# Sheet2.net
KiCad netlist of a schematic drawn in Altium Designer
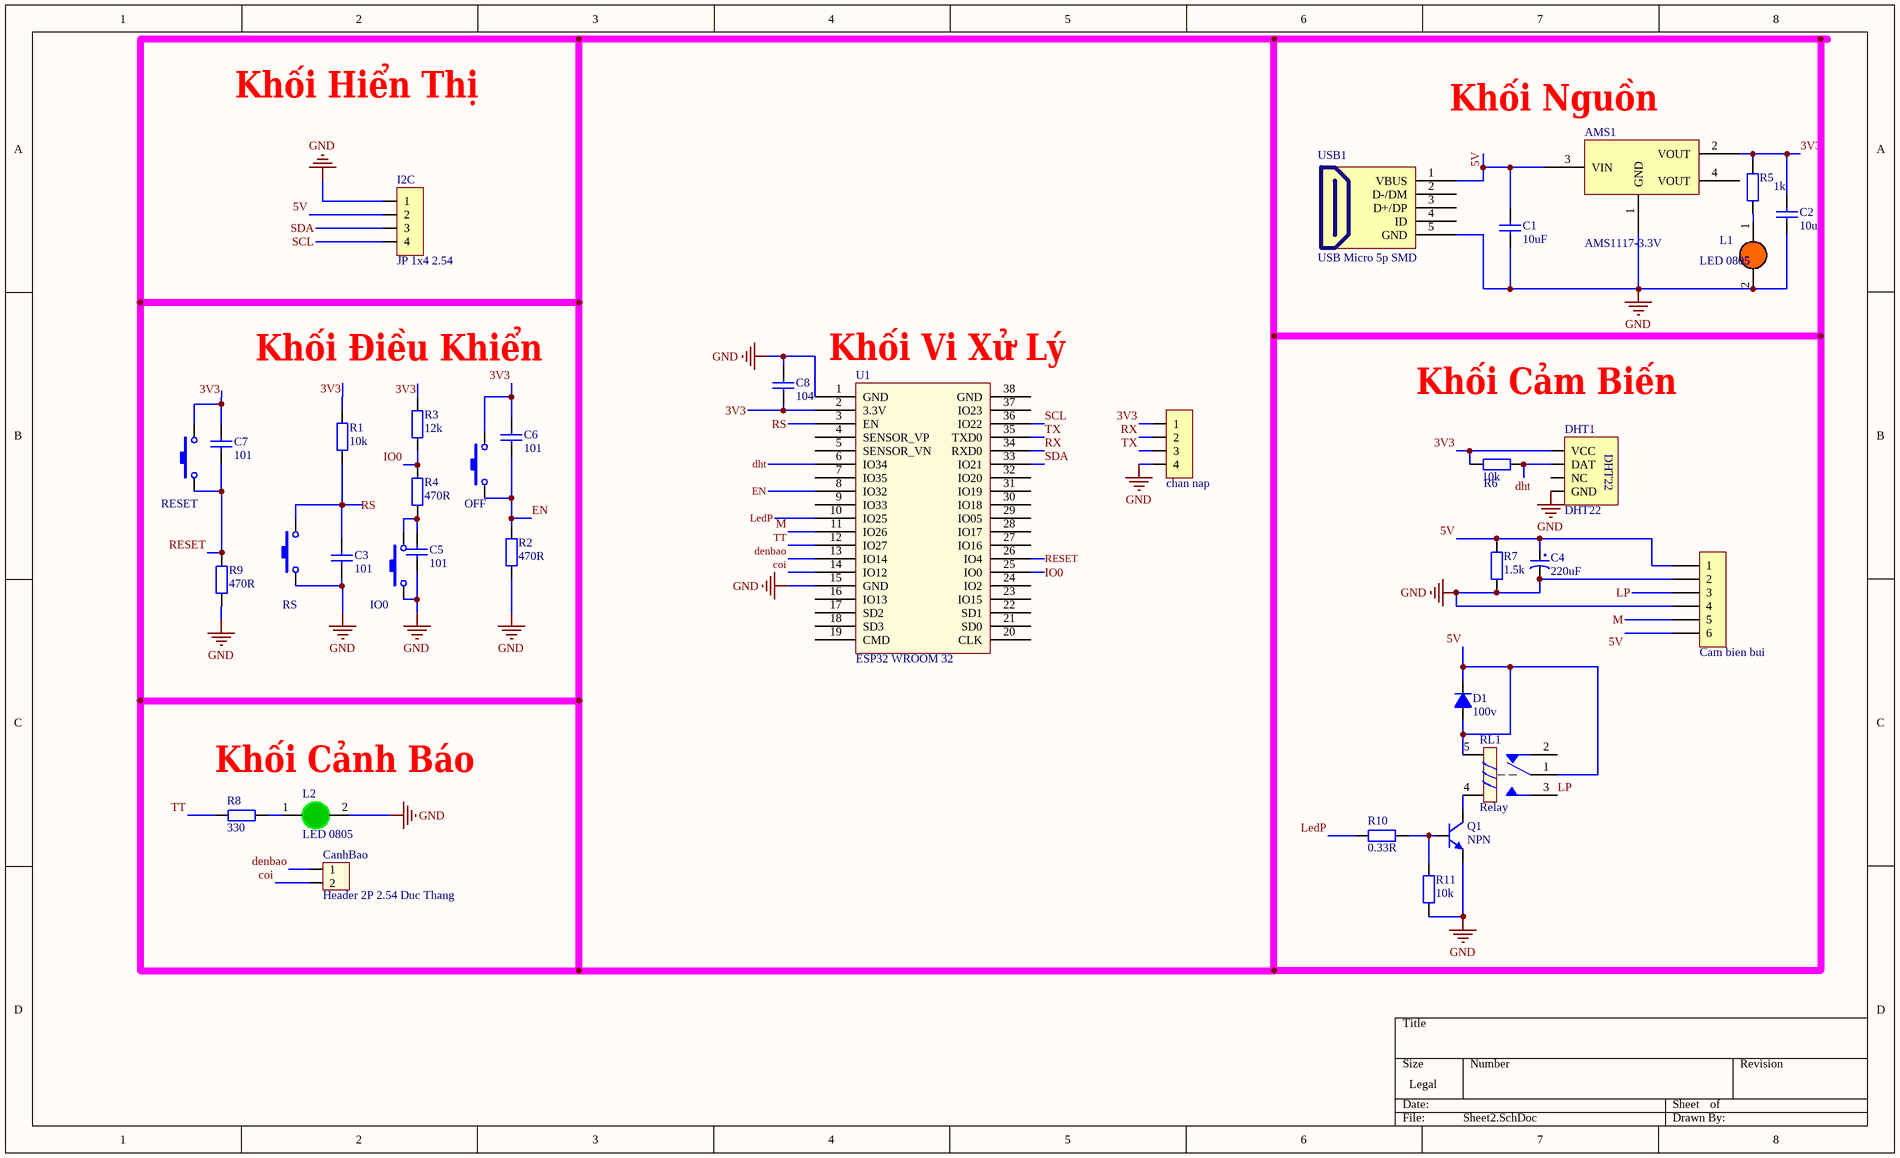
[diagram p0: Sheet2.SchDoc]

(export (version "E")
  (design (tool "Eeschema 10.0.6"))
  (components
    (comp (ref "AMS1")
      (value "AMS1117-3.3V")
      (footprint "SOT223")
      (description "Dán")
      (libsource (lib "Altium_Lib_by_KhueNguyenCreator") (part "AMS1117 SMD"))
    )
    (comp (ref "C1")
      (value "10uF")
      (footprint "tu 0805")
      (description "Dán")
      (libsource (lib "Altium_Lib_by_KhueNguyenCreator") (part "Tu 0805 10pF 50V 10%"))
    )
    (comp (ref "C2")
      (value "10uF")
      (footprint "tu 0805")
      (description "Dán")
      (libsource (lib "Altium_Lib_by_KhueNguyenCreator") (part "Tu 0805 10pF 50V 10%"))
    )
    (comp (ref "C3")
      (value "101")
      (footprint "tu 0805")
      (description "Dán")
      (libsource (lib "Altium_Lib_by_KhueNguyenCreator") (part "Tu 0805 101 50V 20%"))
    )
    (comp (ref "C4")
      (value "220uF")
      (footprint "Tu hoa 5mm")
      (description "Cắm")
      (libsource (lib "Altium_Lib_by_KhueNguyenCreator") (part "Tu Hoa 220uF 16V 6x11"))
    )
    (comp (ref "C5")
      (value "101")
      (footprint "tu 0805")
      (description "Dán")
      (libsource (lib "Altium_Lib_by_KhueNguyenCreator") (part "Tu 0805 101 50V 20%"))
    )
    (comp (ref "C6")
      (value "101")
      (footprint "tu 0805")
      (description "Dán")
      (libsource (lib "Altium_Lib_by_KhueNguyenCreator") (part "Tu 0805 101 50V 20%"))
    )
    (comp (ref "C7")
      (value "101")
      (footprint "tu 0805")
      (description "Dán")
      (libsource (lib "Altium_Lib_by_KhueNguyenCreator") (part "Tu 0805 101 50V 20%"))
    )
    (comp (ref "C8")
      (value "104")
      (footprint "tu gom")
      (description "Cắm")
      (libsource (lib "Altium_Lib_by_KhueNguyenCreator") (part "Tu gom 104 50V"))
    )
    (comp (ref "Cam bien bui")
      (value "Cam bien bui")
      (footprint "XH2.54M-6")
      (description "Cắm")
      (libsource (lib "Altium_Lib_by_KhueNguyenCreator") (part "Header 6P 2.54 Duc Thang"))
    )
    (comp (ref "CanhBao")
      (value "Header 2P 2.54 Duc Thang")
      (footprint "XH2.54M-2")
      (description "Cắm")
      (libsource (lib "Altium_Lib_by_KhueNguyenCreator") (part "Header 2P 2.54 Duc Thang"))
    )
    (comp (ref "D1")
      (value "100v")
      (footprint "DIODE 1A")
      (description "Cắm")
      (libsource (lib "Altium_Lib_by_KhueNguyenCreator") (part "Diode 1N4007"))
    )
    (comp (ref "DHT1")
      (value "DHT22")
      (footprint "DHT22")
      (fields
        (field (name "MANUFACTURER") "Würth Elektronik eiSos GmbH")
        (field (name "PARTNO") "613004143121")
        (field (name "CREATED BY") "Karrer Zheng")
      )
      (libsource (lib "LIBRARY") (part "DHT22"))
    )
    (comp (ref "I2C")
      (value "JP 1x4 2.54")
      (footprint "JP 1x4 DT")
      (description "Cắm")
      (libsource (lib "Altium_Lib_by_KhueNguyenCreator") (part "JP 1x4 2.54 Duc Thang"))
    )
    (comp (ref "IO0")
      (value "Nut Nhan 2 Chan SMD 3x6x2.5")
      (footprint "Nut Nhan 2 Chan SMD 3x6x2.5")
      (libsource (lib "Altium_Lib_by_KhueNguyenCreator") (part "Nut Nhan 2 Chan SMD 3x6x2.5"))
    )
    (comp (ref "JP1")
      (value "chan nap")
      (footprint "JP 1x4 CT")
      (description "Cắm")
      (libsource (lib "Altium_Lib_by_KhueNguyenCreator") (part "JP 1x4 2.54 Cai Thang"))
    )
    (comp (ref "L1")
      (value "LED 0805")
      (footprint "LED-0805-Orange")
      (description "Dán")
      (libsource (lib "Altium_Lib_by_KhueNguyenCreator") (part "LED 0805 Cam"))
    )
    (comp (ref "L2")
      (value "LED 0805")
      (footprint "LED-0805-Green")
      (description "Dán")
      (libsource (lib "Altium_Lib_by_KhueNguyenCreator") (part "LED 0805 Xanh La"))
    )
    (comp (ref "OFF")
      (value "Nut Nhan 2 Chan SMD 3x6x2.5")
      (footprint "Nut Nhan 2 Chan SMD 3x6x2.5")
      (libsource (lib "Altium_Lib_by_KhueNguyenCreator") (part "Nut Nhan 2 Chan SMD 3x6x2.5"))
    )
    (comp (ref "Q1")
      (value "NPN")
      (footprint "TRAN-LOWPOWER")
      (description "NPN General")
      (fields (field (name "PUBLISHER") "Altium Limited"))
      (libsource (lib "my Library") (part "NPN"))
    )
    (comp (ref "R1")
      (value "10k")
      (footprint "tro smd 0805")
      (description "Dán")
      (libsource (lib "Altium_Lib_by_KhueNguyenCreator") (part "Tro 0805 1% 10k"))
    )
    (comp (ref "R2")
      (value "470R")
      (footprint "Tro SMD 0805")
      (description "Dán")
      (libsource (lib "Altium_Lib_by_KhueNguyenCreator") (part "Tro 0805 5% 470R"))
    )
    (comp (ref "R3")
      (value "12k")
      (footprint "tro smd 0805")
      (description "Dán")
      (libsource (lib "Altium_Lib_by_KhueNguyenCreator") (part "Tro 0805 5% 12k"))
    )
    (comp (ref "R4")
      (value "470R")
      (footprint "Tro SMD 0805")
      (description "Dán")
      (libsource (lib "Altium_Lib_by_KhueNguyenCreator") (part "Tro 0805 5% 470R"))
    )
    (comp (ref "R5")
      (value "1k")
      (footprint "tro smd 0805")
      (description "Dán")
      (libsource (lib "Altium_Lib_by_KhueNguyenCreator") (part "Tro 0805 1% 1k"))
    )
    (comp (ref "R6")
      (value "10k")
      (footprint "tro smd 0805")
      (description "Dán")
      (libsource (lib "Altium_Lib_by_KhueNguyenCreator") (part "Tro 0805 5% 10k"))
    )
    (comp (ref "R7")
      (value "1.5k")
      (footprint "tro vach 1/4w")
      (description "Cắm")
      (libsource (lib "Altium_Lib_by_KhueNguyenCreator") (part "Tro Vach 1/4W 5% 1.5k"))
    )
    (comp (ref "R8")
      (value "330")
      (footprint "Tro SMD 0805")
      (description "Dán")
      (libsource (lib "Altium_Lib_by_KhueNguyenCreator") (part "Tro 0805 5% 470R"))
    )
    (comp (ref "R9")
      (value "470R")
      (footprint "Tro SMD 0805")
      (description "Dán")
      (libsource (lib "Altium_Lib_by_KhueNguyenCreator") (part "Tro 0805 5% 470R"))
    )
    (comp (ref "R10")
      (value "0.33R")
      (footprint "tro vach 1/2w")
      (description "Cắm")
      (libsource (lib "Altium_Lib_by_KhueNguyenCreator") (part "Tro Vach 1/2W 5% 0.33R"))
    )
    (comp (ref "R11")
      (value "10k")
      (footprint "tro vach 1/2w")
      (description "Cắm")
      (libsource (lib "Altium_Lib_by_KhueNguyenCreator") (part "Tro Vach 1/2W 5% 10k"))
    )
    (comp (ref "RESET")
      (value "Nut Nhan 2 Chan SMD 3x6x2.5")
      (footprint "Nut Nhan 2 Chan SMD 3x6x2.5")
      (libsource (lib "Altium_Lib_by_KhueNguyenCreator") (part "Nut Nhan 2 Chan SMD 3x6x2.5"))
    )
    (comp (ref "RL1")
      (value "Relay")
      (footprint "Relay 5 Chan SRD")
      (description "Relay 5 Chan")
      (libsource (lib "Altium_Lib_by_KhueNguyenCreator") (part "Relay 5 Chan SRD"))
    )
    (comp (ref "RS")
      (value "Nut Nhan 2 Chan SMD 3x6x2.5")
      (footprint "Nut Nhan 2 Chan SMD 3x6x2.5")
      (libsource (lib "Altium_Lib_by_KhueNguyenCreator") (part "Nut Nhan 2 Chan SMD 3x6x2.5"))
    )
    (comp (ref "U1")
      (value "ESP32 WROOM 32")
      (footprint "ESP32-WROOM-32D")
      (libsource (lib "Altium_Lib_by_KhueNguyenCreator") (part "ESP32 WROOM 32"))
    )
    (comp (ref "USB1")
      (value "USB Micro 5p SMD")
      (footprint "USB Micro 5p SMD")
      (description "USB Type B")
      (libsource (lib "Altium_Lib_by_KhueNguyenCreator") (part "USB Micro 5p SMD"))
    )
  )
  (nets
    (net (code "1") (name "/3V3") (class "Default")
      (node (ref "AMS1") (pin "2") (pinfunction "VOUT_2") (pintype "passive"))
      (node (ref "C2") (pin "1") (pinfunction "1_1") (pintype "passive"))
      (node (ref "C6") (pin "1") (pinfunction "1_1") (pintype "passive"))
      (node (ref "C7") (pin "1") (pinfunction "1_1") (pintype "passive"))
      (node (ref "C8") (pin "2") (pinfunction "2_2") (pintype "passive"))
      (node (ref "DHT1") (pin "1") (pinfunction "VCC_1") (pintype "passive"))
      (node (ref "JP1") (pin "1") (pinfunction "1_1") (pintype "passive"))
      (node (ref "OFF") (pin "2") (pinfunction "2_2") (pintype "passive"))
      (node (ref "R1") (pin "2") (pinfunction "2_2") (pintype "passive"))
      (node (ref "R3") (pin "2") (pinfunction "2_2") (pintype "passive"))
      (node (ref "R5") (pin "2") (pinfunction "2_2") (pintype "passive"))
      (node (ref "R6") (pin "1") (pinfunction "1_1") (pintype "passive"))
      (node (ref "RESET") (pin "2") (pinfunction "2_2") (pintype "passive"))
      (node (ref "U1") (pin "2") (pinfunction "3.3V_2") (pintype "passive"))
    )
    (net (code "2") (name "/5V") (class "Default")
      (node (ref "AMS1") (pin "3") (pinfunction "VIN_3") (pintype "passive"))
      (node (ref "C1") (pin "1") (pinfunction "1_1") (pintype "passive"))
      (node (ref "C4") (pin "1") (pinfunction "1_1") (pintype "passive"))
      (node (ref "Cam bien bui") (pin "1") (pinfunction "1_1") (pintype "passive"))
      (node (ref "Cam bien bui") (pin "6") (pinfunction "6_6") (pintype "passive"))
      (node (ref "D1") (pin "1") (pinfunction "A_1") (pintype "passive"))
      (node (ref "D1") (pin "2") (pinfunction "K_2") (pintype "passive"))
      (node (ref "I2C") (pin "2") (pinfunction "2_2") (pintype "passive"))
      (node (ref "R7") (pin "2") (pinfunction "2_2") (pintype "passive"))
      (node (ref "RL1") (pin "1") (pinfunction "1_1") (pintype "passive"))
      (node (ref "RL1") (pin "5") (pinfunction "5_5") (pintype "passive"))
      (node (ref "USB1") (pin "1") (pinfunction "VBUS_1") (pintype "passive"))
    )
    (net (code "3") (name "/EN") (class "Default")
      (node (ref "C6") (pin "2") (pinfunction "2_2") (pintype "passive"))
      (node (ref "OFF") (pin "1") (pinfunction "1_1") (pintype "passive"))
      (node (ref "R2") (pin "2") (pinfunction "2_2") (pintype "passive"))
      (node (ref "U1") (pin "8") (pinfunction "IO32_8") (pintype "passive"))
    )
    (net (code "4") (name "/IO0") (class "Default")
      (node (ref "R3") (pin "1") (pinfunction "1_1") (pintype "passive"))
      (node (ref "R4") (pin "2") (pinfunction "2_2") (pintype "passive"))
      (node (ref "U1") (pin "25") (pinfunction "IO0_25") (pintype "passive"))
    )
    (net (code "5") (name "/LP") (class "Default")
      (node (ref "Cam bien bui") (pin "3") (pinfunction "3_3") (pintype "passive"))
      (node (ref "RL1") (pin "3") (pinfunction "3_3") (pintype "passive"))
    )
    (net (code "6") (name "/LedP") (class "Default")
      (node (ref "R10") (pin "1") (pinfunction "1_1") (pintype "passive"))
      (node (ref "U1") (pin "10") (pinfunction "IO25_10") (pintype "passive"))
    )
    (net (code "7") (name "/M") (class "Default")
      (node (ref "Cam bien bui") (pin "5") (pinfunction "5_5") (pintype "passive"))
      (node (ref "U1") (pin "11") (pinfunction "IO26_11") (pintype "passive"))
    )
    (net (code "8") (name "/RESET") (class "Default")
      (node (ref "C7") (pin "2") (pinfunction "2_2") (pintype "passive"))
      (node (ref "R9") (pin "2") (pinfunction "2_2") (pintype "passive"))
      (node (ref "RESET") (pin "1") (pinfunction "1_1") (pintype "passive"))
      (node (ref "U1") (pin "26") (pinfunction "IO4_26") (pintype "passive"))
    )
    (net (code "9") (name "/RS") (class "Default")
      (node (ref "C3") (pin "1") (pinfunction "1_1") (pintype "passive"))
      (node (ref "R1") (pin "1") (pinfunction "1_1") (pintype "passive"))
      (node (ref "RS") (pin "2") (pinfunction "2_2") (pintype "passive"))
      (node (ref "U1") (pin "3") (pinfunction "EN_3") (pintype "passive"))
    )
    (net (code "10") (name "/RX") (class "Default")
      (node (ref "JP1") (pin "2") (pinfunction "2_2") (pintype "passive"))
      (node (ref "U1") (pin "34") (pinfunction "RXD0_34") (pintype "passive"))
    )
    (net (code "11") (name "/SCL") (class "Default")
      (node (ref "I2C") (pin "4") (pinfunction "4_4") (pintype "passive"))
      (node (ref "U1") (pin "36") (pinfunction "IO22_36") (pintype "passive"))
    )
    (net (code "12") (name "/SDA") (class "Default")
      (node (ref "I2C") (pin "3") (pinfunction "3_3") (pintype "passive"))
      (node (ref "U1") (pin "33") (pinfunction "IO21_33") (pintype "passive"))
    )
    (net (code "13") (name "/TT") (class "Default")
      (node (ref "R8") (pin "2") (pinfunction "2_2") (pintype "passive"))
      (node (ref "U1") (pin "12") (pinfunction "IO27_12") (pintype "passive"))
    )
    (net (code "14") (name "/TX") (class "Default")
      (node (ref "JP1") (pin "3") (pinfunction "3_3") (pintype "passive"))
      (node (ref "U1") (pin "35") (pinfunction "TXD0_35") (pintype "passive"))
    )
    (net (code "15") (name "/coi") (class "Default")
      (node (ref "CanhBao") (pin "2") (pinfunction "2_2") (pintype "passive"))
      (node (ref "U1") (pin "14") (pinfunction "IO12_14") (pintype "passive"))
    )
    (net (code "16") (name "/denbao") (class "Default")
      (node (ref "CanhBao") (pin "1") (pinfunction "1_1") (pintype "passive"))
      (node (ref "U1") (pin "13") (pinfunction "IO14_13") (pintype "passive"))
    )
    (net (code "17") (name "/dht") (class "Default")
      (node (ref "DHT1") (pin "2") (pinfunction "DAT_2") (pintype "passive"))
      (node (ref "R6") (pin "2") (pinfunction "2_2") (pintype "passive"))
      (node (ref "U1") (pin "6") (pinfunction "IO34_6") (pintype "passive"))
    )
    (net (code "18") (name "GND") (class "Default")
      (node (ref "AMS1") (pin "1") (pinfunction "GND_1") (pintype "passive"))
      (node (ref "C1") (pin "2") (pinfunction "2_2") (pintype "passive"))
      (node (ref "C2") (pin "2") (pinfunction "2_2") (pintype "passive"))
      (node (ref "C3") (pin "2") (pinfunction "2_2") (pintype "passive"))
      (node (ref "C4") (pin "2") (pinfunction "2_2") (pintype "passive"))
      (node (ref "C5") (pin "2") (pinfunction "2_2") (pintype "passive"))
      (node (ref "C8") (pin "1") (pinfunction "1_1") (pintype "passive"))
      (node (ref "Cam bien bui") (pin "2") (pinfunction "2_2") (pintype "passive"))
      (node (ref "Cam bien bui") (pin "4") (pinfunction "4_4") (pintype "passive"))
      (node (ref "DHT1") (pin "4") (pinfunction "GND_4") (pintype "passive"))
      (node (ref "I2C") (pin "1") (pinfunction "1_1") (pintype "passive"))
      (node (ref "IO0") (pin "1") (pinfunction "1_1") (pintype "passive"))
      (node (ref "JP1") (pin "4") (pinfunction "4_4") (pintype "passive"))
      (node (ref "L1") (pin "2") (pinfunction "K_2") (pintype "passive"))
      (node (ref "L2") (pin "2") (pinfunction "K_2") (pintype "passive"))
      (node (ref "Q1") (pin "3") (pinfunction "E_3") (pintype "passive"))
      (node (ref "R11") (pin "1") (pinfunction "1_1") (pintype "passive"))
      (node (ref "R2") (pin "1") (pinfunction "1_1") (pintype "passive"))
      (node (ref "R7") (pin "1") (pinfunction "1_1") (pintype "passive"))
      (node (ref "R9") (pin "1") (pinfunction "1_1") (pintype "passive"))
      (node (ref "RS") (pin "1") (pinfunction "1_1") (pintype "passive"))
      (node (ref "U1") (pin "1") (pinfunction "GND_1") (pintype "passive"))
      (node (ref "U1") (pin "15") (pinfunction "GND_15") (pintype "passive"))
      (node (ref "USB1") (pin "5") (pinfunction "GND_5") (pintype "passive"))
    )
    (net (code "19") (name "Net-(C5-Pad1)") (class "Default")
      (node (ref "C5") (pin "1") (pinfunction "1_1") (pintype "passive"))
      (node (ref "IO0") (pin "2") (pinfunction "2_2") (pintype "passive"))
      (node (ref "R4") (pin "1") (pinfunction "1_1") (pintype "passive"))
    )
    (net (code "20") (name "Net-(L1-A)") (class "Default")
      (node (ref "L1") (pin "1") (pinfunction "A_1") (pintype "passive"))
      (node (ref "R5") (pin "1") (pinfunction "1_1") (pintype "passive"))
    )
    (net (code "21") (name "Net-(L2-A)") (class "Default")
      (node (ref "L2") (pin "1") (pinfunction "A_1") (pintype "passive"))
      (node (ref "R8") (pin "1") (pinfunction "1_1") (pintype "passive"))
    )
    (net (code "22") (name "Net-(Q1-B)") (class "Default")
      (node (ref "Q1") (pin "1") (pinfunction "B_1") (pintype "passive"))
      (node (ref "R10") (pin "2") (pinfunction "2_2") (pintype "passive"))
      (node (ref "R11") (pin "2") (pinfunction "2_2") (pintype "passive"))
    )
    (net (code "23") (name "Net-(Q1-C)") (class "Default")
      (node (ref "Q1") (pin "2") (pinfunction "C_2") (pintype "passive"))
      (node (ref "RL1") (pin "4") (pinfunction "4_4") (pintype "passive"))
    )
    (net (code "24") (name "unconnected-(AMS1-VOUT-Pad4)") (class "Default")
      (node (ref "AMS1") (pin "4") (pinfunction "VOUT_4") (pintype "passive"))
    )
    (net (code "25") (name "unconnected-(DHT1-NC-Pad3)") (class "Default")
      (node (ref "DHT1") (pin "3") (pinfunction "NC_3") (pintype "passive"))
    )
    (net (code "26") (name "unconnected-(RL1-Pad2)") (class "Default")
      (node (ref "RL1") (pin "2") (pinfunction "2_2") (pintype "passive"))
    )
    (net (code "27") (name "unconnected-(U1-CLK-Pad20)") (class "Default")
      (node (ref "U1") (pin "20") (pinfunction "CLK_20") (pintype "passive"))
    )
    (net (code "28") (name "unconnected-(U1-CMD-Pad19)") (class "Default")
      (node (ref "U1") (pin "19") (pinfunction "CMD_19") (pintype "passive"))
    )
    (net (code "29") (name "unconnected-(U1-GND-Pad38)") (class "Default")
      (node (ref "U1") (pin "38") (pinfunction "GND_38") (pintype "passive"))
    )
    (net (code "30") (name "unconnected-(U1-IO2-Pad24)") (class "Default")
      (node (ref "U1") (pin "24") (pinfunction "IO2_24") (pintype "passive"))
    )
    (net (code "31") (name "unconnected-(U1-IO05-Pad29)") (class "Default")
      (node (ref "U1") (pin "29") (pinfunction "IO05_29") (pintype "passive"))
    )
    (net (code "32") (name "unconnected-(U1-IO13-Pad16)") (class "Default")
      (node (ref "U1") (pin "16") (pinfunction "IO13_16") (pintype "passive"))
    )
    (net (code "33") (name "unconnected-(U1-IO15-Pad23)") (class "Default")
      (node (ref "U1") (pin "23") (pinfunction "IO15_23") (pintype "passive"))
    )
    (net (code "34") (name "unconnected-(U1-IO16-Pad27)") (class "Default")
      (node (ref "U1") (pin "27") (pinfunction "IO16_27") (pintype "passive"))
    )
    (net (code "35") (name "unconnected-(U1-IO17-Pad28)") (class "Default")
      (node (ref "U1") (pin "28") (pinfunction "IO17_28") (pintype "passive"))
    )
    (net (code "36") (name "unconnected-(U1-IO18-Pad30)") (class "Default")
      (node (ref "U1") (pin "30") (pinfunction "IO18_30") (pintype "passive"))
    )
    (net (code "37") (name "unconnected-(U1-IO19-Pad31)") (class "Default")
      (node (ref "U1") (pin "31") (pinfunction "IO19_31") (pintype "passive"))
    )
    (net (code "38") (name "unconnected-(U1-IO20-Pad32)") (class "Default")
      (node (ref "U1") (pin "32") (pinfunction "IO20_32") (pintype "passive"))
    )
    (net (code "39") (name "unconnected-(U1-IO23-Pad37)") (class "Default")
      (node (ref "U1") (pin "37") (pinfunction "IO23_37") (pintype "passive"))
    )
    (net (code "40") (name "unconnected-(U1-IO33-Pad9)") (class "Default")
      (node (ref "U1") (pin "9") (pinfunction "IO33_9") (pintype "passive"))
    )
    (net (code "41") (name "unconnected-(U1-IO35-Pad7)") (class "Default")
      (node (ref "U1") (pin "7") (pinfunction "IO35_7") (pintype "passive"))
    )
    (net (code "42") (name "unconnected-(U1-SD0-Pad21)") (class "Default")
      (node (ref "U1") (pin "21") (pinfunction "SD0_21") (pintype "passive"))
    )
    (net (code "43") (name "unconnected-(U1-SD1-Pad22)") (class "Default")
      (node (ref "U1") (pin "22") (pinfunction "SD1_22") (pintype "passive"))
    )
    (net (code "44") (name "unconnected-(U1-SD2-Pad17)") (class "Default")
      (node (ref "U1") (pin "17") (pinfunction "SD2_17") (pintype "passive"))
    )
    (net (code "45") (name "unconnected-(U1-SD3-Pad18)") (class "Default")
      (node (ref "U1") (pin "18") (pinfunction "SD3_18") (pintype "passive"))
    )
    (net (code "46") (name "unconnected-(U1-SENSOR_VN-Pad5)") (class "Default")
      (node (ref "U1") (pin "5") (pinfunction "SENSOR_VN_5") (pintype "passive"))
    )
    (net (code "47") (name "unconnected-(U1-SENSOR_VP-Pad4)") (class "Default")
      (node (ref "U1") (pin "4") (pinfunction "SENSOR_VP_4") (pintype "passive"))
    )
    (net (code "48") (name "unconnected-(USB1-D+{slash}DP-Pad3)") (class "Default")
      (node (ref "USB1") (pin "3") (pinfunction "D+/DP_3") (pintype "passive"))
    )
    (net (code "49") (name "unconnected-(USB1-D-{slash}DM-Pad2)") (class "Default")
      (node (ref "USB1") (pin "2") (pinfunction "D-/DM_2") (pintype "passive"))
    )
    (net (code "50") (name "unconnected-(USB1-ID-Pad4)") (class "Default")
      (node (ref "USB1") (pin "4") (pinfunction "ID_4") (pintype "passive"))
    )
  )
)
